# conv_smd_new.net
KiCad netlist of a schematic drawn in EAGLE
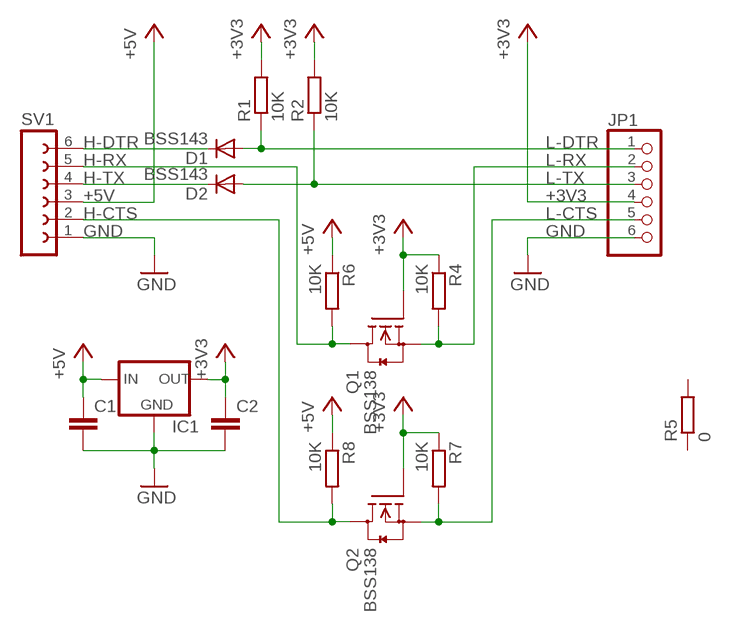
[diagram p0: schematic, sheet 1]

(export (version "E")
  (design (tool "Eeschema 10.0.6"))
  (components
    (comp (ref "C1")
      (value "C-EUC0805")
      (footprint "eagle-import:C0805")
      (libsource (lib "eagle-import") (part "C-EUC0805"))
    )
    (comp (ref "C2")
      (value "C-EUC0805")
      (footprint "eagle-import:C0805")
      (libsource (lib "eagle-import") (part "C-EUC0805"))
    )
    (comp (ref "D1")
      (value "BSS143")
      (footprint "eagle-import:SOD80C")
      (libsource (lib "eagle-import") (part "DIODE-SOD80C"))
    )
    (comp (ref "D2")
      (value "BSS143")
      (footprint "eagle-import:SOD80C")
      (libsource (lib "eagle-import") (part "DIODE-SOD80C"))
    )
    (comp (ref "IC1")
      (value "MCP1700_SOT-32")
      (footprint "eagle-import:SOT23")
      (libsource (lib "eagle-import") (part "MCP1700_SOT-32"))
    )
    (comp (ref "JP1")
      (value "PINHD-1X6/90")
      (footprint "eagle-import:1X06_90")
      (libsource (lib "eagle-import") (part "PINHD-1X6/90"))
    )
    (comp (ref "Q1")
      (value "BSS138")
      (footprint "eagle-import:SOT23")
      (libsource (lib "eagle-import") (part "BSS138"))
    )
    (comp (ref "Q2")
      (value "BSS138")
      (footprint "eagle-import:SOT23")
      (libsource (lib "eagle-import") (part "BSS138"))
    )
    (comp (ref "R1")
      (value "10K")
      (footprint "eagle-import:M0805")
      (libsource (lib "eagle-import") (part "R-EU_M0805"))
    )
    (comp (ref "R2")
      (value "10K")
      (footprint "eagle-import:M0805")
      (libsource (lib "eagle-import") (part "R-EU_M0805"))
    )
    (comp (ref "R4")
      (value "10K")
      (footprint "eagle-import:M0805")
      (libsource (lib "eagle-import") (part "R-EU_M0805"))
    )
    (comp (ref "R5")
      (value "0")
      (footprint "eagle-import:M1206")
      (libsource (lib "eagle-import") (part "R-EU_M1206"))
    )
    (comp (ref "R6")
      (value "10K")
      (footprint "eagle-import:M0805")
      (libsource (lib "eagle-import") (part "R-EU_M0805"))
    )
    (comp (ref "R7")
      (value "10K")
      (footprint "eagle-import:M0805")
      (libsource (lib "eagle-import") (part "R-EU_M0805"))
    )
    (comp (ref "R8")
      (value "10K")
      (footprint "eagle-import:M0805")
      (libsource (lib "eagle-import") (part "R-EU_M0805"))
    )
    (comp (ref "SV1")
      (value "FE06W")
      (footprint "eagle-import:FE06W")
      (libsource (lib "eagle-import") (part "FE06W"))
    )
  )
  (nets
    (net (code "1") (name "+3V3") (class "Default")
      (node (ref "C2") (pin "1") (pinfunction "1_1") (pintype "passive"))
      (node (ref "IC1") (pin "2") (pinfunction "OUT_2") (pintype "passive"))
      (node (ref "JP1") (pin "4") (pinfunction "4_4") (pintype "passive"))
      (node (ref "Q1") (pin "1") (pinfunction "G_1") (pintype "passive"))
      (node (ref "Q2") (pin "1") (pinfunction "G_1") (pintype "passive"))
      (node (ref "R1") (pin "2") (pinfunction "2_2") (pintype "passive"))
      (node (ref "R2") (pin "2") (pinfunction "2_2") (pintype "passive"))
      (node (ref "R4") (pin "1") (pinfunction "1_1") (pintype "passive"))
      (node (ref "R7") (pin "1") (pinfunction "1_1") (pintype "passive"))
    )
    (net (code "2") (name "+5V") (class "Default")
      (node (ref "C1") (pin "1") (pinfunction "1_1") (pintype "passive"))
      (node (ref "IC1") (pin "3") (pinfunction "IN_3") (pintype "input"))
      (node (ref "R6") (pin "1") (pinfunction "1_1") (pintype "passive"))
      (node (ref "R8") (pin "1") (pinfunction "1_1") (pintype "passive"))
      (node (ref "SV1") (pin "3") (pinfunction "3_3") (pintype "passive"))
    )
    (net (code "3") (name "/H-CTS") (class "Default")
      (node (ref "Q2") (pin "3") (pinfunction "D_3") (pintype "passive"))
      (node (ref "R8") (pin "2") (pinfunction "2_2") (pintype "passive"))
      (node (ref "SV1") (pin "2") (pinfunction "2_2") (pintype "passive"))
    )
    (net (code "4") (name "/H-DTR") (class "Default")
      (node (ref "D1") (pin "C") (pinfunction "C_C") (pintype "passive"))
      (node (ref "SV1") (pin "6") (pinfunction "6_6") (pintype "passive"))
    )
    (net (code "5") (name "/H-RX") (class "Default")
      (node (ref "Q1") (pin "3") (pinfunction "D_3") (pintype "passive"))
      (node (ref "R6") (pin "2") (pinfunction "2_2") (pintype "passive"))
      (node (ref "SV1") (pin "5") (pinfunction "5_5") (pintype "passive"))
    )
    (net (code "6") (name "/H-TX") (class "Default")
      (node (ref "D2") (pin "C") (pinfunction "C_C") (pintype "passive"))
      (node (ref "SV1") (pin "4") (pinfunction "4_4") (pintype "passive"))
    )
    (net (code "7") (name "/L-CTS") (class "Default")
      (node (ref "JP1") (pin "5") (pinfunction "5_5") (pintype "passive"))
      (node (ref "Q2") (pin "2") (pinfunction "S_2") (pintype "passive"))
      (node (ref "R7") (pin "2") (pinfunction "2_2") (pintype "passive"))
    )
    (net (code "8") (name "/L-DTR") (class "Default")
      (node (ref "D1") (pin "A") (pinfunction "A_A") (pintype "passive"))
      (node (ref "JP1") (pin "1") (pinfunction "1_1") (pintype "passive"))
      (node (ref "R1") (pin "1") (pinfunction "1_1") (pintype "passive"))
    )
    (net (code "9") (name "/L-RX") (class "Default")
      (node (ref "JP1") (pin "2") (pinfunction "2_2") (pintype "passive"))
      (node (ref "Q1") (pin "2") (pinfunction "S_2") (pintype "passive"))
      (node (ref "R4") (pin "2") (pinfunction "2_2") (pintype "passive"))
    )
    (net (code "10") (name "/L-TX") (class "Default")
      (node (ref "D2") (pin "A") (pinfunction "A_A") (pintype "passive"))
      (node (ref "JP1") (pin "3") (pinfunction "3_3") (pintype "passive"))
      (node (ref "R2") (pin "1") (pinfunction "1_1") (pintype "passive"))
    )
    (net (code "11") (name "GND") (class "Default")
      (node (ref "C1") (pin "2") (pinfunction "2_2") (pintype "passive"))
      (node (ref "C2") (pin "2") (pinfunction "2_2") (pintype "passive"))
      (node (ref "IC1") (pin "1") (pinfunction "GND_1") (pintype "input"))
      (node (ref "JP1") (pin "6") (pinfunction "6_6") (pintype "passive"))
      (node (ref "SV1") (pin "1") (pinfunction "1_1") (pintype "passive"))
    )
    (net (code "12") (name "unconnected-(R5-Pad1)") (class "Default")
      (node (ref "R5") (pin "1") (pinfunction "1_1") (pintype "passive"))
    )
    (net (code "13") (name "unconnected-(R5-Pad2)") (class "Default")
      (node (ref "R5") (pin "2") (pinfunction "2_2") (pintype "passive"))
    )
  )
)
